# Sheet1.net
KiCad netlist of a schematic drawn in Altium Designer
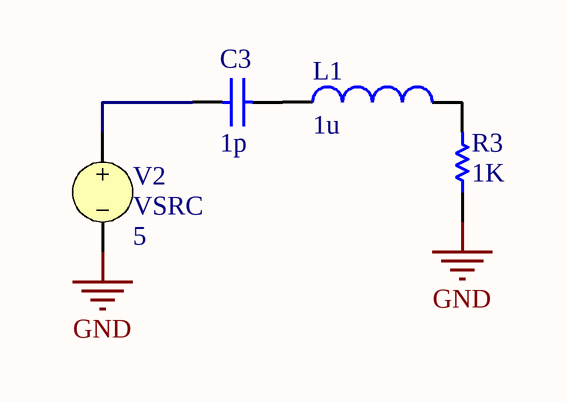
[diagram p0: Sheet1.SchDoc]

(export (version "E")
  (design (tool "Eeschema 10.0.6"))
  (components
    (comp (ref "C3")
      (value "1p")
      (description "Capacitor")
      (libsource (lib "Simulation Generic Components") (part "Capacitor"))
    )
    (comp (ref "L1")
      (value "1u")
      (description "Inductor")
      (libsource (lib "Simulation Generic Components") (part "Inductor"))
    )
    (comp (ref "R3")
      (value "1K")
      (description "Resistor")
      (libsource (lib "Simulation Generic Components") (part "Resistor"))
    )
    (comp (ref "V2")
      (value "VSRC")
      (description "Voltage Source")
      (fields (field (name "ALTIUM_VALUE") "5") (field (name "PUBLISHER") "Altium Limited"))
      (libsource (lib "Simulation Generic Components") (part "VSRC"))
    )
  )
  (nets
    (net (code "1") (name "GND") (class "Default")
      (node (ref "R3") (pin "1") (pinfunction "1_1") (pintype "passive"))
      (node (ref "V2") (pin "2") (pinfunction "2_2") (pintype "passive"))
    )
    (net (code "2") (name "Net-(C3-Pad1)") (class "Default")
      (node (ref "C3") (pin "1") (pinfunction "1_1") (pintype "passive"))
      (node (ref "V2") (pin "1") (pinfunction "1_1") (pintype "passive"))
    )
    (net (code "3") (name "Net-(C3-Pad2)") (class "Default")
      (node (ref "C3") (pin "2") (pinfunction "2_2") (pintype "passive"))
      (node (ref "L1") (pin "1") (pinfunction "1_1") (pintype "passive"))
    )
    (net (code "4") (name "Net-(L1-Pad2)") (class "Default")
      (node (ref "L1") (pin "2") (pinfunction "2_2") (pintype "passive"))
      (node (ref "R3") (pin "2") (pinfunction "2_2") (pintype "passive"))
    )
  )
)
